# PB.net
KiCad netlist of a schematic drawn in EAGLE
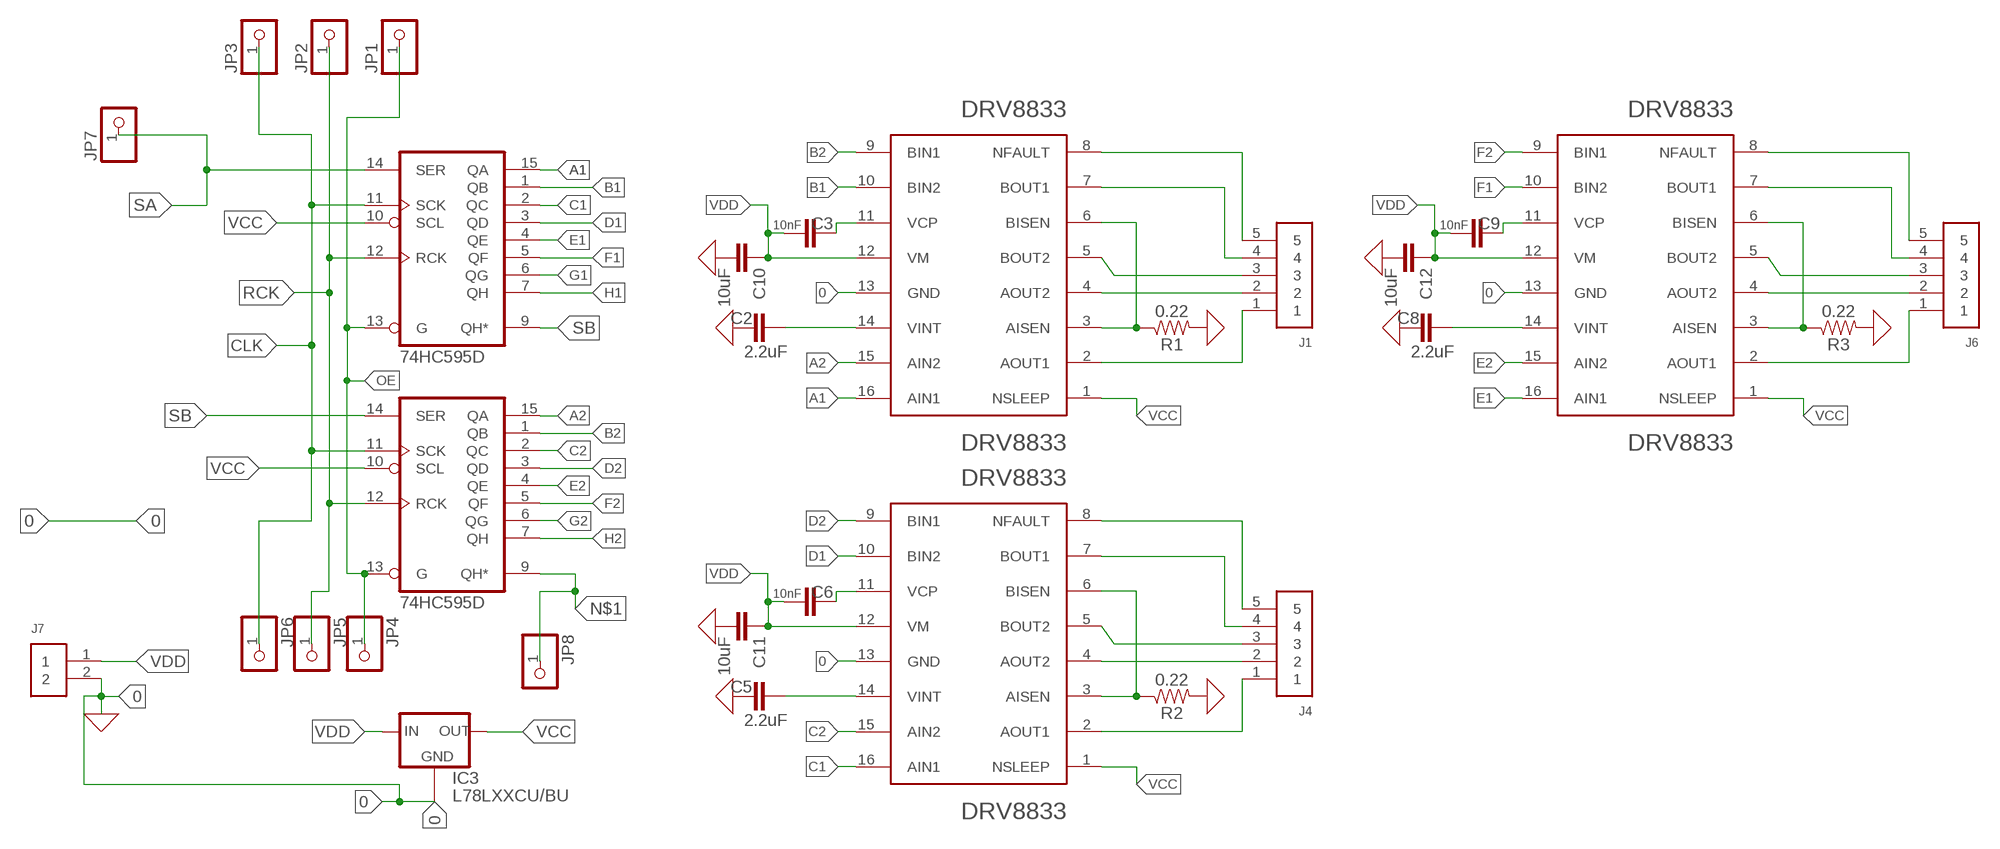
[diagram p0: schematic, sheet 1]

(export (version "E")
  (design (tool "Eeschema 10.0.6"))
  (components
    (comp (ref "C2")
      (value "2.2uF")
      (footprint "eagle-import:0603")
      (libsource (lib "eagle-import") (part "2.2UF-0603-10V-20%"))
    )
    (comp (ref "C3")
      (value "10nF")
      (footprint "eagle-import:0603")
      (libsource (lib "eagle-import") (part "10NF-0603-50V-10%"))
    )
    (comp (ref "C5")
      (value "2.2uF")
      (footprint "eagle-import:0603")
      (libsource (lib "eagle-import") (part "2.2UF-0603-10V-20%"))
    )
    (comp (ref "C6")
      (value "10nF")
      (footprint "eagle-import:0603")
      (libsource (lib "eagle-import") (part "10NF-0603-50V-10%"))
    )
    (comp (ref "C8")
      (value "2.2uF")
      (footprint "eagle-import:0603")
      (libsource (lib "eagle-import") (part "2.2UF-0603-10V-20%"))
    )
    (comp (ref "C9")
      (value "10nF")
      (footprint "eagle-import:0603")
      (libsource (lib "eagle-import") (part "10NF-0603-50V-10%"))
    )
    (comp (ref "C10")
      (value "10uF")
      (footprint "eagle-import:0805")
      (libsource (lib "eagle-import") (part "10UF-0805-10V-10%"))
    )
    (comp (ref "C11")
      (value "10uF")
      (footprint "eagle-import:0805")
      (libsource (lib "eagle-import") (part "10UF-0805-10V-10%"))
    )
    (comp (ref "C12")
      (value "10uF")
      (footprint "eagle-import:0805")
      (libsource (lib "eagle-import") (part "10UF-0805-10V-10%"))
    )
    (comp (ref "DRV8833PWP1")
      (value "DRV8833")
      (footprint "eagle-import:SOP65P640X120-17N")
      (libsource (lib "eagle-import") (part "DRV8833"))
    )
    (comp (ref "DRV8833PWP2")
      (value "DRV8833")
      (footprint "eagle-import:SOP65P640X120-17N")
      (libsource (lib "eagle-import") (part "DRV8833"))
    )
    (comp (ref "DRV8833PWP3")
      (value "DRV8833")
      (footprint "eagle-import:SOP65P640X120-17N")
      (libsource (lib "eagle-import") (part "DRV8833"))
    )
    (comp (ref "IC1")
      (value "74HC595D")
      (footprint "eagle-import:SO16")
      (libsource (lib "eagle-import") (part "74595DHC"))
    )
    (comp (ref "IC2")
      (value "74HC595D")
      (footprint "eagle-import:SO16")
      (libsource (lib "eagle-import") (part "74595DHC"))
    )
    (comp (ref "IC3")
      (value "L78LXXCU/BU")
      (footprint "eagle-import:SOT89")
      (libsource (lib "eagle-import") (part "L78LXXCU/BU"))
    )
    (comp (ref "J1")
      (value "61300511121")
      (footprint "eagle-import:61300511121")
      (fields
        (field (name "DIGI_KEY_PART_NUMBER") "732-5318-ND")
        (field (name "MANUFACTURER") "Wurth Electronics Inc.")
        (field (name "CREATED_BY") "PCBLayout.com")
      )
      (libsource (lib "eagle-import") (part "61300511121"))
    )
    (comp (ref "J4")
      (value "61300511121")
      (footprint "eagle-import:61300511121")
      (fields
        (field (name "DIGI_KEY_PART_NUMBER") "732-5318-ND")
        (field (name "MANUFACTURER") "Wurth Electronics Inc.")
        (field (name "CREATED_BY") "PCBLayout.com")
      )
      (libsource (lib "eagle-import") (part "61300511121"))
    )
    (comp (ref "J6")
      (value "61300511121")
      (footprint "eagle-import:61300511121")
      (fields
        (field (name "DIGI_KEY_PART_NUMBER") "732-5318-ND")
        (field (name "MANUFACTURER") "Wurth Electronics Inc.")
        (field (name "CREATED_BY") "PCBLayout.com")
      )
      (libsource (lib "eagle-import") (part "61300511121"))
    )
    (comp (ref "J7")
      (value "61300211121")
      (footprint "eagle-import:61300211121")
      (fields
        (field (name "DIGI_KEY_PART_NUMBER") "732-5315-ND")
        (field (name "MANUFACTURER") "Wurth Electronics Inc.")
        (field (name "CREATED_BY") "PCBLayout.com")
      )
      (libsource (lib "eagle-import") (part "61300211121"))
    )
    (comp (ref "JP1")
      (value "PINHD-1X1")
      (footprint "eagle-import:1X01")
      (libsource (lib "eagle-import") (part "PINHD-1X1"))
    )
    (comp (ref "JP2")
      (value "PINHD-1X1")
      (footprint "eagle-import:1X01")
      (libsource (lib "eagle-import") (part "PINHD-1X1"))
    )
    (comp (ref "JP3")
      (value "PINHD-1X1")
      (footprint "eagle-import:1X01")
      (libsource (lib "eagle-import") (part "PINHD-1X1"))
    )
    (comp (ref "JP4")
      (value "PINHD-1X1")
      (footprint "eagle-import:1X01")
      (libsource (lib "eagle-import") (part "PINHD-1X1"))
    )
    (comp (ref "JP5")
      (value "PINHD-1X1")
      (footprint "eagle-import:1X01")
      (libsource (lib "eagle-import") (part "PINHD-1X1"))
    )
    (comp (ref "JP6")
      (value "PINHD-1X1")
      (footprint "eagle-import:1X01")
      (libsource (lib "eagle-import") (part "PINHD-1X1"))
    )
    (comp (ref "JP7")
      (value "PINHD-1X1")
      (footprint "eagle-import:1X01")
      (libsource (lib "eagle-import") (part "PINHD-1X1"))
    )
    (comp (ref "JP8")
      (value "PINHD-1X1")
      (footprint "eagle-import:1X01")
      (libsource (lib "eagle-import") (part "PINHD-1X1"))
    )
    (comp (ref "R1")
      (value "0.22")
      (footprint "eagle-import:0805")
      (libsource (lib "eagle-import") (part "0.22OHM-0805-1/4W-1%"))
    )
    (comp (ref "R2")
      (value "0.22")
      (footprint "eagle-import:0805")
      (libsource (lib "eagle-import") (part "0.22OHM-0805-1/4W-1%"))
    )
    (comp (ref "R3")
      (value "0.22")
      (footprint "eagle-import:0805")
      (libsource (lib "eagle-import") (part "0.22OHM-0805-1/4W-1%"))
    )
  )
  (nets
    (net (code "1") (name "0") (class "Default")
      (node (ref "C10") (pin "2") (pinfunction "2_2") (pintype "passive"))
      (node (ref "C11") (pin "2") (pinfunction "2_2") (pintype "passive"))
      (node (ref "C12") (pin "2") (pinfunction "2_2") (pintype "passive"))
      (node (ref "C2") (pin "2") (pinfunction "2_2") (pintype "passive"))
      (node (ref "C5") (pin "2") (pinfunction "2_2") (pintype "passive"))
      (node (ref "C8") (pin "2") (pinfunction "2_2") (pintype "passive"))
      (node (ref "DRV8833PWP1") (pin "13") (pinfunction "GND_13") (pintype "bidirectional"))
      (node (ref "DRV8833PWP2") (pin "13") (pinfunction "GND_13") (pintype "bidirectional"))
      (node (ref "DRV8833PWP3") (pin "13") (pinfunction "GND_13") (pintype "bidirectional"))
      (node (ref "IC3") (pin "4") (pinfunction "GND1_4") (pintype "input"))
      (node (ref "J7") (pin "2") (pinfunction "2_2") (pintype "passive"))
      (node (ref "R1") (pin "2") (pinfunction "2_2") (pintype "passive"))
      (node (ref "R2") (pin "2") (pinfunction "2_2") (pintype "passive"))
      (node (ref "R3") (pin "2") (pinfunction "2_2") (pintype "passive"))
    )
    (net (code "2") (name "A1") (class "Default")
      (node (ref "DRV8833PWP1") (pin "16") (pinfunction "AIN1_16") (pintype "bidirectional"))
      (node (ref "IC1") (pin "15") (pinfunction "QA_15") (pintype "tri_state"))
    )
    (net (code "3") (name "A2") (class "Default")
      (node (ref "DRV8833PWP1") (pin "15") (pinfunction "AIN2_15") (pintype "bidirectional"))
      (node (ref "IC2") (pin "15") (pinfunction "QA_15") (pintype "tri_state"))
    )
    (net (code "4") (name "B1") (class "Default")
      (node (ref "DRV8833PWP1") (pin "10") (pinfunction "BIN2_10") (pintype "bidirectional"))
      (node (ref "IC1") (pin "1") (pinfunction "QB_1") (pintype "tri_state"))
    )
    (net (code "5") (name "B2") (class "Default")
      (node (ref "DRV8833PWP1") (pin "9") (pinfunction "BIN1_9") (pintype "bidirectional"))
      (node (ref "IC2") (pin "1") (pinfunction "QB_1") (pintype "tri_state"))
    )
    (net (code "6") (name "C1") (class "Default")
      (node (ref "DRV8833PWP2") (pin "16") (pinfunction "AIN1_16") (pintype "bidirectional"))
      (node (ref "IC1") (pin "2") (pinfunction "QC_2") (pintype "tri_state"))
    )
    (net (code "7") (name "C2") (class "Default")
      (node (ref "DRV8833PWP2") (pin "15") (pinfunction "AIN2_15") (pintype "bidirectional"))
      (node (ref "IC2") (pin "2") (pinfunction "QC_2") (pintype "tri_state"))
    )
    (net (code "8") (name "CLK") (class "Default")
      (node (ref "IC1") (pin "11") (pinfunction "SCK_11") (pintype "input"))
      (node (ref "IC2") (pin "11") (pinfunction "SCK_11") (pintype "input"))
      (node (ref "JP3") (pin "1") (pinfunction "1_1") (pintype "passive"))
      (node (ref "JP6") (pin "1") (pinfunction "1_1") (pintype "passive"))
    )
    (net (code "9") (name "D1") (class "Default")
      (node (ref "DRV8833PWP2") (pin "10") (pinfunction "BIN2_10") (pintype "bidirectional"))
      (node (ref "IC1") (pin "3") (pinfunction "QD_3") (pintype "tri_state"))
    )
    (net (code "10") (name "D2") (class "Default")
      (node (ref "DRV8833PWP2") (pin "9") (pinfunction "BIN1_9") (pintype "bidirectional"))
      (node (ref "IC2") (pin "3") (pinfunction "QD_3") (pintype "tri_state"))
    )
    (net (code "11") (name "E1") (class "Default")
      (node (ref "DRV8833PWP3") (pin "16") (pinfunction "AIN1_16") (pintype "bidirectional"))
      (node (ref "IC1") (pin "4") (pinfunction "QE_4") (pintype "tri_state"))
    )
    (net (code "12") (name "E2") (class "Default")
      (node (ref "DRV8833PWP3") (pin "15") (pinfunction "AIN2_15") (pintype "bidirectional"))
      (node (ref "IC2") (pin "4") (pinfunction "QE_4") (pintype "tri_state"))
    )
    (net (code "13") (name "F1") (class "Default")
      (node (ref "DRV8833PWP3") (pin "10") (pinfunction "BIN2_10") (pintype "bidirectional"))
      (node (ref "IC1") (pin "5") (pinfunction "QF_5") (pintype "tri_state"))
    )
    (net (code "14") (name "F2") (class "Default")
      (node (ref "DRV8833PWP3") (pin "9") (pinfunction "BIN1_9") (pintype "bidirectional"))
      (node (ref "IC2") (pin "5") (pinfunction "QF_5") (pintype "tri_state"))
    )
    (net (code "15") (name "G1") (class "Default")
      (node (ref "IC1") (pin "6") (pinfunction "QG_6") (pintype "tri_state"))
    )
    (net (code "16") (name "G2") (class "Default")
      (node (ref "IC2") (pin "6") (pinfunction "QG_6") (pintype "tri_state"))
    )
    (net (code "17") (name "H1") (class "Default")
      (node (ref "IC1") (pin "7") (pinfunction "QH_7") (pintype "tri_state"))
    )
    (net (code "18") (name "H2") (class "Default")
      (node (ref "IC2") (pin "7") (pinfunction "QH_7") (pintype "tri_state"))
    )
    (net (code "19") (name "N$1") (class "Default")
      (node (ref "IC2") (pin "9") (pinfunction "QH*_9") (pintype "tri_state"))
      (node (ref "JP8") (pin "1") (pinfunction "1_1") (pintype "passive"))
    )
    (net (code "20") (name "Net-(DRV8833PWP1-AISEN)") (class "Default")
      (node (ref "DRV8833PWP1") (pin "3") (pinfunction "AISEN_3") (pintype "bidirectional"))
      (node (ref "DRV8833PWP1") (pin "6") (pinfunction "BISEN_6") (pintype "bidirectional"))
      (node (ref "R1") (pin "1") (pinfunction "1_1") (pintype "passive"))
    )
    (net (code "21") (name "Net-(DRV8833PWP1-AOUT1)") (class "Default")
      (node (ref "DRV8833PWP1") (pin "2") (pinfunction "AOUT1_2") (pintype "bidirectional"))
      (node (ref "J1") (pin "1") (pinfunction "1_1") (pintype "passive"))
    )
    (net (code "22") (name "Net-(DRV8833PWP1-AOUT2)") (class "Default")
      (node (ref "DRV8833PWP1") (pin "4") (pinfunction "AOUT2_4") (pintype "bidirectional"))
      (node (ref "J1") (pin "2") (pinfunction "2_2") (pintype "passive"))
    )
    (net (code "23") (name "Net-(DRV8833PWP1-BOUT1)") (class "Default")
      (node (ref "DRV8833PWP1") (pin "7") (pinfunction "BOUT1_7") (pintype "bidirectional"))
      (node (ref "J1") (pin "4") (pinfunction "4_4") (pintype "passive"))
    )
    (net (code "24") (name "Net-(DRV8833PWP1-BOUT2)") (class "Default")
      (node (ref "DRV8833PWP1") (pin "5") (pinfunction "BOUT2_5") (pintype "bidirectional"))
      (node (ref "J1") (pin "3") (pinfunction "3_3") (pintype "passive"))
    )
    (net (code "25") (name "Net-(DRV8833PWP1-NFAULT)") (class "Default")
      (node (ref "DRV8833PWP1") (pin "8") (pinfunction "NFAULT_8") (pintype "bidirectional"))
      (node (ref "J1") (pin "5") (pinfunction "5_5") (pintype "passive"))
    )
    (net (code "26") (name "Net-(DRV8833PWP1-VCP)") (class "Default")
      (node (ref "C3") (pin "1") (pinfunction "1_1") (pintype "passive"))
      (node (ref "DRV8833PWP1") (pin "11") (pinfunction "VCP_11") (pintype "bidirectional"))
    )
    (net (code "27") (name "Net-(DRV8833PWP1-VINT)") (class "Default")
      (node (ref "C2") (pin "1") (pinfunction "1_1") (pintype "passive"))
      (node (ref "DRV8833PWP1") (pin "14") (pinfunction "VINT_14") (pintype "bidirectional"))
    )
    (net (code "28") (name "Net-(DRV8833PWP2-AISEN)") (class "Default")
      (node (ref "DRV8833PWP2") (pin "3") (pinfunction "AISEN_3") (pintype "bidirectional"))
      (node (ref "DRV8833PWP2") (pin "6") (pinfunction "BISEN_6") (pintype "bidirectional"))
      (node (ref "R2") (pin "1") (pinfunction "1_1") (pintype "passive"))
    )
    (net (code "29") (name "Net-(DRV8833PWP2-AOUT1)") (class "Default")
      (node (ref "DRV8833PWP2") (pin "2") (pinfunction "AOUT1_2") (pintype "bidirectional"))
      (node (ref "J4") (pin "1") (pinfunction "1_1") (pintype "passive"))
    )
    (net (code "30") (name "Net-(DRV8833PWP2-AOUT2)") (class "Default")
      (node (ref "DRV8833PWP2") (pin "4") (pinfunction "AOUT2_4") (pintype "bidirectional"))
      (node (ref "J4") (pin "2") (pinfunction "2_2") (pintype "passive"))
    )
    (net (code "31") (name "Net-(DRV8833PWP2-BOUT1)") (class "Default")
      (node (ref "DRV8833PWP2") (pin "7") (pinfunction "BOUT1_7") (pintype "bidirectional"))
      (node (ref "J4") (pin "4") (pinfunction "4_4") (pintype "passive"))
    )
    (net (code "32") (name "Net-(DRV8833PWP2-BOUT2)") (class "Default")
      (node (ref "DRV8833PWP2") (pin "5") (pinfunction "BOUT2_5") (pintype "bidirectional"))
      (node (ref "J4") (pin "3") (pinfunction "3_3") (pintype "passive"))
    )
    (net (code "33") (name "Net-(DRV8833PWP2-NFAULT)") (class "Default")
      (node (ref "DRV8833PWP2") (pin "8") (pinfunction "NFAULT_8") (pintype "bidirectional"))
      (node (ref "J4") (pin "5") (pinfunction "5_5") (pintype "passive"))
    )
    (net (code "34") (name "Net-(DRV8833PWP2-VCP)") (class "Default")
      (node (ref "C6") (pin "1") (pinfunction "1_1") (pintype "passive"))
      (node (ref "DRV8833PWP2") (pin "11") (pinfunction "VCP_11") (pintype "bidirectional"))
    )
    (net (code "35") (name "Net-(DRV8833PWP2-VINT)") (class "Default")
      (node (ref "C5") (pin "1") (pinfunction "1_1") (pintype "passive"))
      (node (ref "DRV8833PWP2") (pin "14") (pinfunction "VINT_14") (pintype "bidirectional"))
    )
    (net (code "36") (name "Net-(DRV8833PWP3-AISEN)") (class "Default")
      (node (ref "DRV8833PWP3") (pin "3") (pinfunction "AISEN_3") (pintype "bidirectional"))
      (node (ref "DRV8833PWP3") (pin "6") (pinfunction "BISEN_6") (pintype "bidirectional"))
      (node (ref "R3") (pin "1") (pinfunction "1_1") (pintype "passive"))
    )
    (net (code "37") (name "Net-(DRV8833PWP3-AOUT1)") (class "Default")
      (node (ref "DRV8833PWP3") (pin "2") (pinfunction "AOUT1_2") (pintype "bidirectional"))
      (node (ref "J6") (pin "1") (pinfunction "1_1") (pintype "passive"))
    )
    (net (code "38") (name "Net-(DRV8833PWP3-AOUT2)") (class "Default")
      (node (ref "DRV8833PWP3") (pin "4") (pinfunction "AOUT2_4") (pintype "bidirectional"))
      (node (ref "J6") (pin "2") (pinfunction "2_2") (pintype "passive"))
    )
    (net (code "39") (name "Net-(DRV8833PWP3-BOUT1)") (class "Default")
      (node (ref "DRV8833PWP3") (pin "7") (pinfunction "BOUT1_7") (pintype "bidirectional"))
      (node (ref "J6") (pin "4") (pinfunction "4_4") (pintype "passive"))
    )
    (net (code "40") (name "Net-(DRV8833PWP3-BOUT2)") (class "Default")
      (node (ref "DRV8833PWP3") (pin "5") (pinfunction "BOUT2_5") (pintype "bidirectional"))
      (node (ref "J6") (pin "3") (pinfunction "3_3") (pintype "passive"))
    )
    (net (code "41") (name "Net-(DRV8833PWP3-NFAULT)") (class "Default")
      (node (ref "DRV8833PWP3") (pin "8") (pinfunction "NFAULT_8") (pintype "bidirectional"))
      (node (ref "J6") (pin "5") (pinfunction "5_5") (pintype "passive"))
    )
    (net (code "42") (name "Net-(DRV8833PWP3-VCP)") (class "Default")
      (node (ref "C9") (pin "1") (pinfunction "1_1") (pintype "passive"))
      (node (ref "DRV8833PWP3") (pin "11") (pinfunction "VCP_11") (pintype "bidirectional"))
    )
    (net (code "43") (name "Net-(DRV8833PWP3-VINT)") (class "Default")
      (node (ref "C8") (pin "1") (pinfunction "1_1") (pintype "passive"))
      (node (ref "DRV8833PWP3") (pin "14") (pinfunction "VINT_14") (pintype "bidirectional"))
    )
    (net (code "44") (name "OE") (class "Default")
      (node (ref "IC1") (pin "13") (pinfunction "G_13") (pintype "input"))
      (node (ref "IC2") (pin "13") (pinfunction "G_13") (pintype "input"))
      (node (ref "JP1") (pin "1") (pinfunction "1_1") (pintype "passive"))
      (node (ref "JP4") (pin "1") (pinfunction "1_1") (pintype "passive"))
    )
    (net (code "45") (name "RCK") (class "Default")
      (node (ref "IC1") (pin "12") (pinfunction "RCK_12") (pintype "input"))
      (node (ref "IC2") (pin "12") (pinfunction "RCK_12") (pintype "input"))
      (node (ref "JP2") (pin "1") (pinfunction "1_1") (pintype "passive"))
      (node (ref "JP5") (pin "1") (pinfunction "1_1") (pintype "passive"))
    )
    (net (code "46") (name "SA") (class "Default")
      (node (ref "IC1") (pin "14") (pinfunction "SER_14") (pintype "input"))
      (node (ref "JP7") (pin "1") (pinfunction "1_1") (pintype "passive"))
    )
    (net (code "47") (name "SB") (class "Default")
      (node (ref "IC1") (pin "9") (pinfunction "QH*_9") (pintype "tri_state"))
      (node (ref "IC2") (pin "14") (pinfunction "SER_14") (pintype "input"))
    )
    (net (code "48") (name "VCC") (class "Default")
      (node (ref "DRV8833PWP1") (pin "1") (pinfunction "NSLEEP_1") (pintype "bidirectional"))
      (node (ref "DRV8833PWP2") (pin "1") (pinfunction "NSLEEP_1") (pintype "bidirectional"))
      (node (ref "DRV8833PWP3") (pin "1") (pinfunction "NSLEEP_1") (pintype "bidirectional"))
      (node (ref "IC1") (pin "10") (pinfunction "SCL_10") (pintype "input"))
      (node (ref "IC2") (pin "10") (pinfunction "SCL_10") (pintype "input"))
      (node (ref "IC3") (pin "1") (pinfunction "OUT_1") (pintype "passive"))
    )
    (net (code "49") (name "VDD") (class "Default")
      (node (ref "C10") (pin "1") (pinfunction "1_1") (pintype "passive"))
      (node (ref "C11") (pin "1") (pinfunction "1_1") (pintype "passive"))
      (node (ref "C12") (pin "1") (pinfunction "1_1") (pintype "passive"))
      (node (ref "C3") (pin "2") (pinfunction "2_2") (pintype "passive"))
      (node (ref "C6") (pin "2") (pinfunction "2_2") (pintype "passive"))
      (node (ref "C9") (pin "2") (pinfunction "2_2") (pintype "passive"))
      (node (ref "DRV8833PWP1") (pin "12") (pinfunction "VM_12") (pintype "bidirectional"))
      (node (ref "DRV8833PWP2") (pin "12") (pinfunction "VM_12") (pintype "bidirectional"))
      (node (ref "DRV8833PWP3") (pin "12") (pinfunction "VM_12") (pintype "bidirectional"))
      (node (ref "IC3") (pin "3") (pinfunction "IN_3") (pintype "input"))
      (node (ref "J7") (pin "1") (pinfunction "1_1") (pintype "passive"))
    )
    (net (code "50") (name "unconnected-(IC3-GND-Pad2)") (class "Default")
      (node (ref "IC3") (pin "2") (pinfunction "GND_2") (pintype "input"))
    )
  )
)
